# AuxPDU.net
KiCad netlist of a schematic drawn in Altium Designer
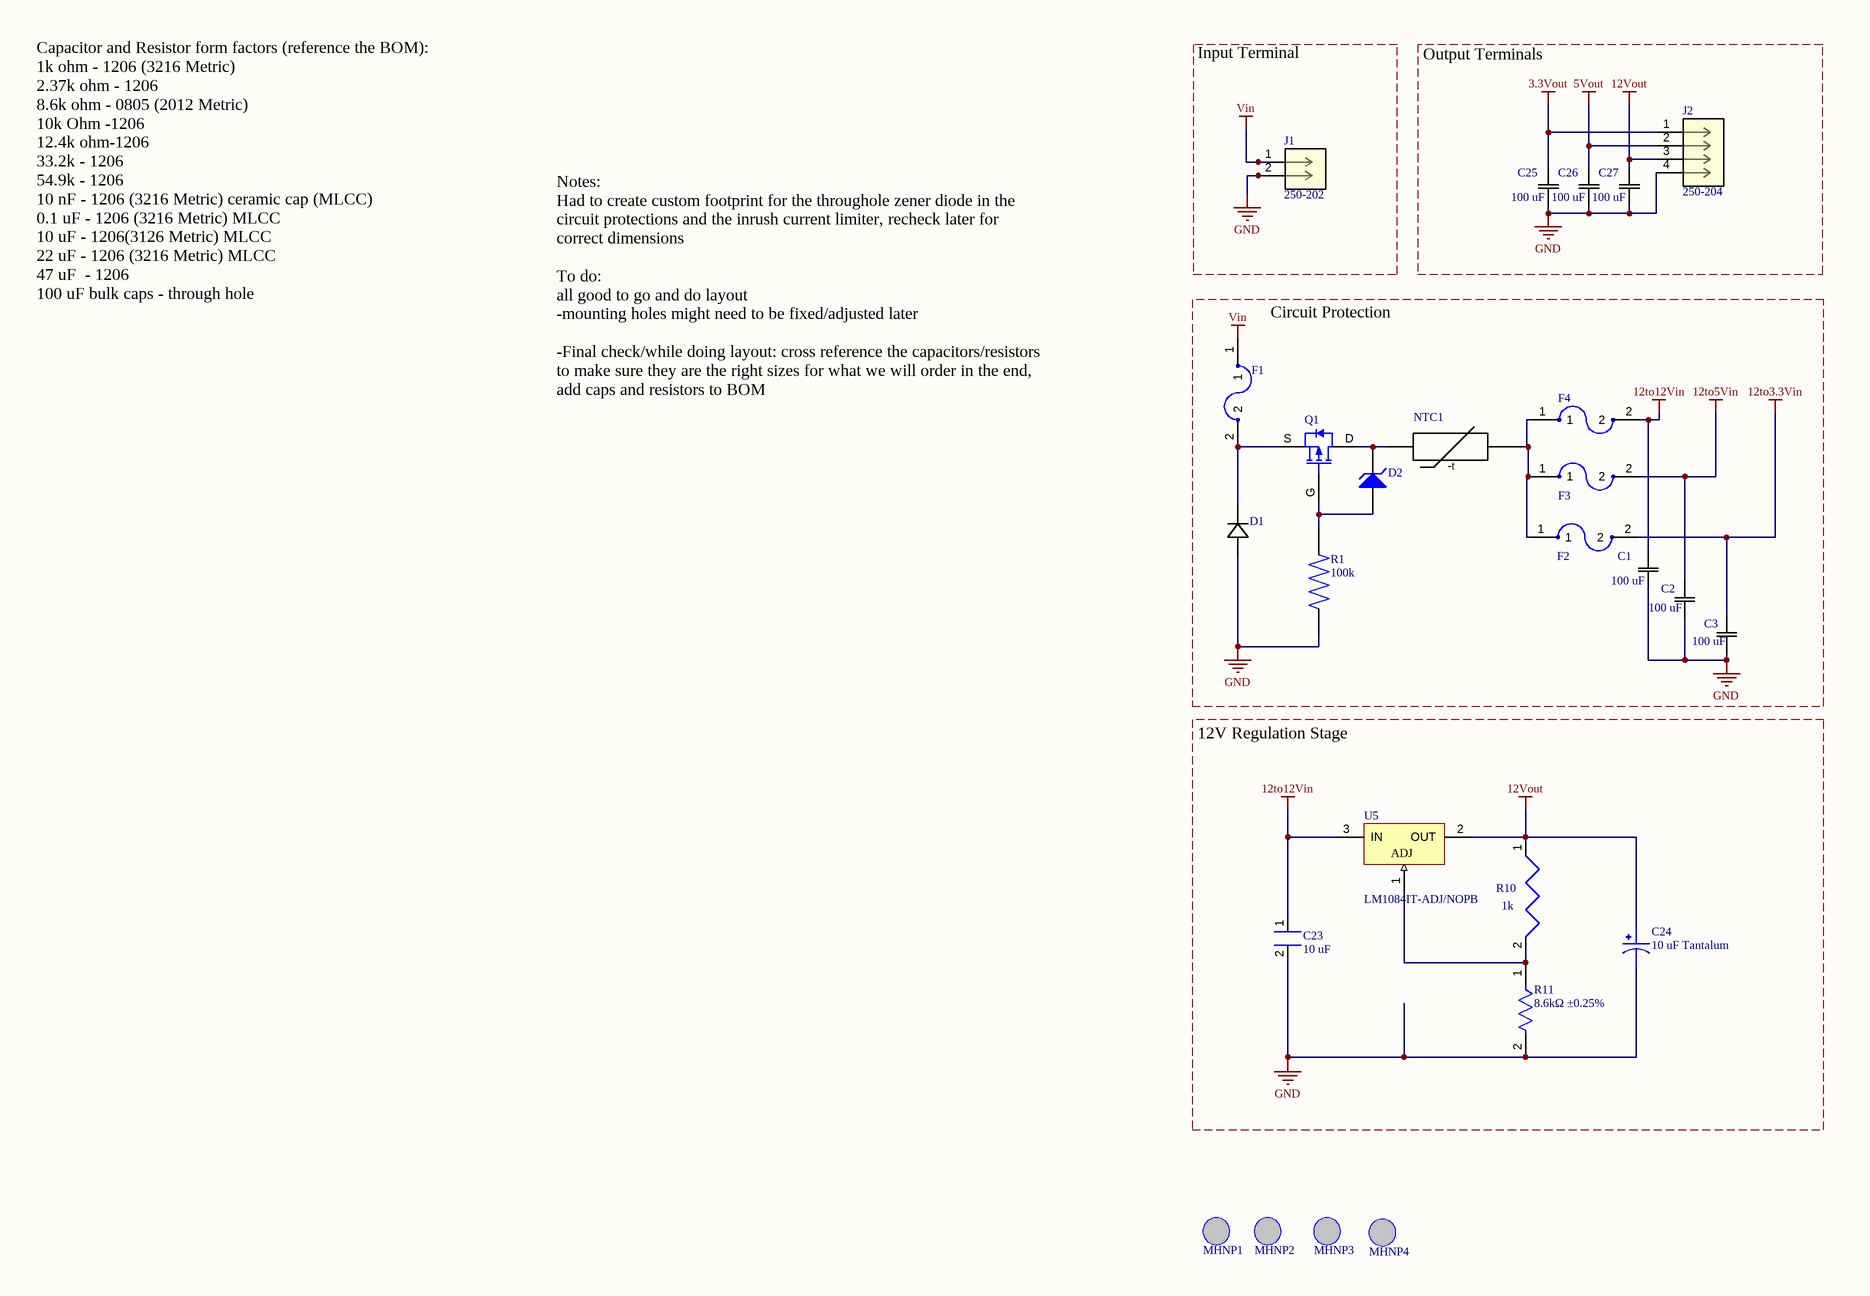
[diagram p0: AuxPDU.SchDoc, left]
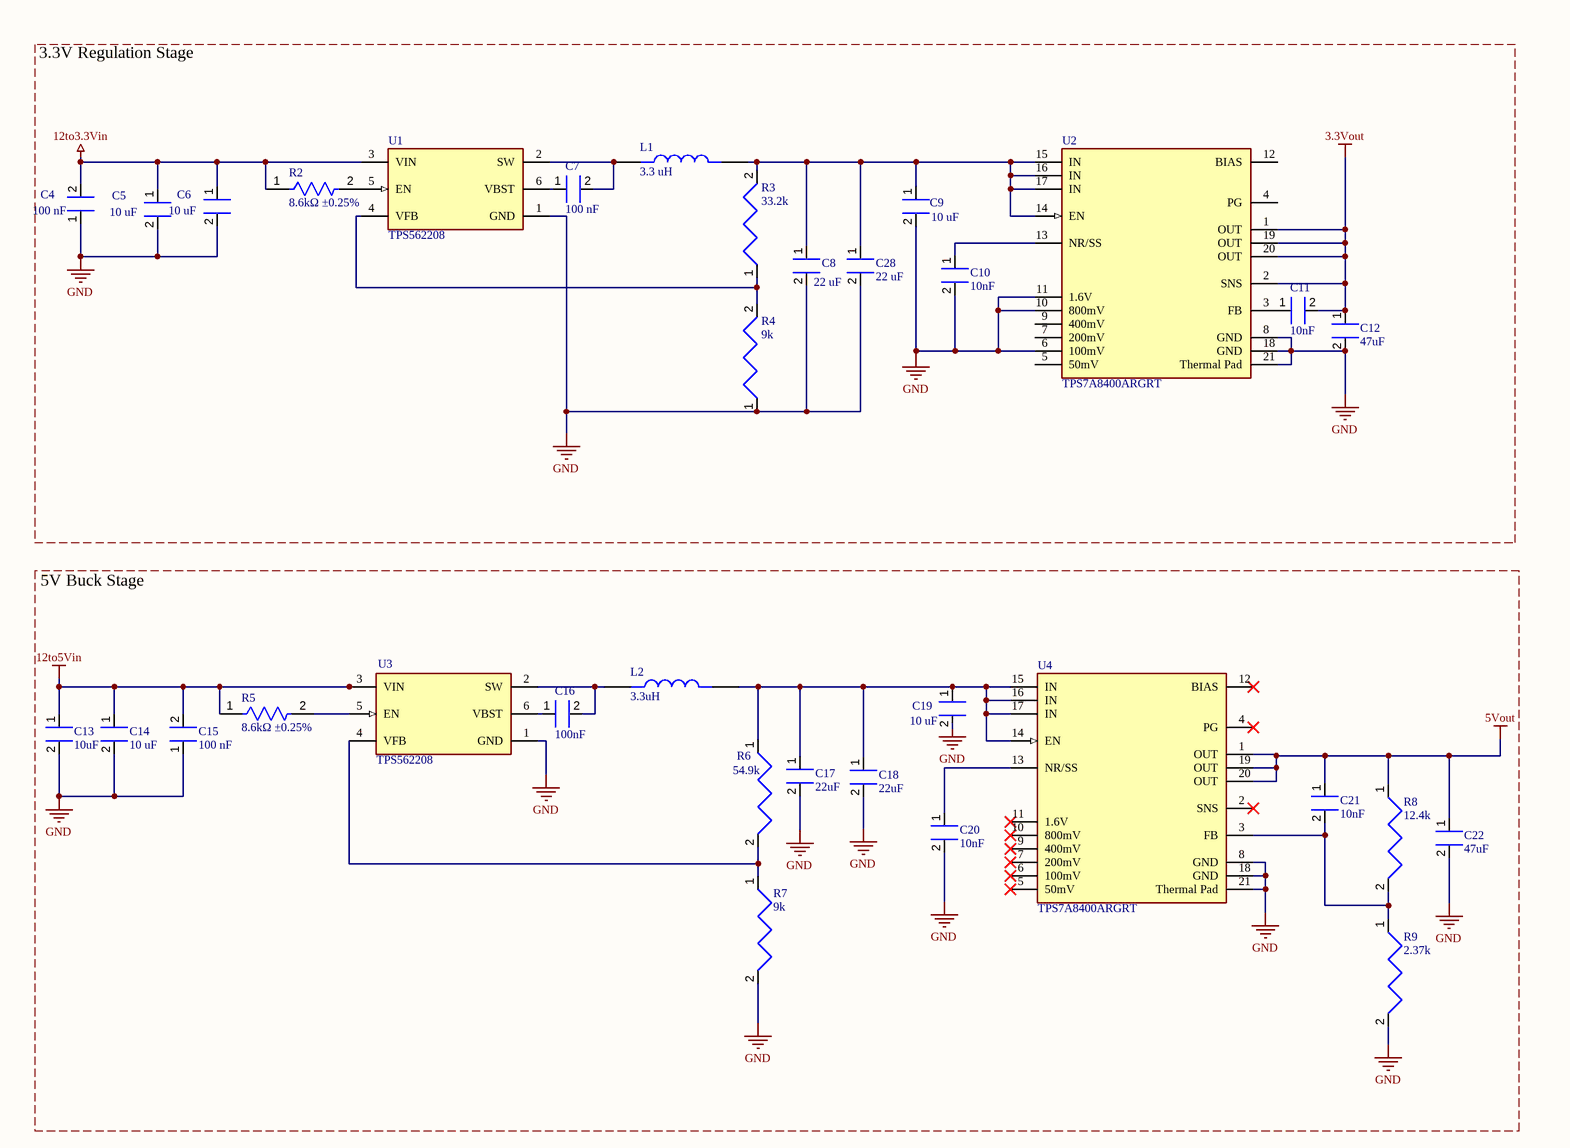
[diagram p1: AuxPDU.SchDoc, right]

(export (version "E")
  (design (tool "Eeschema 10.0.6"))
  (components
    (comp (ref "C1")
      (value "100 uF")
      (footprint "CAP_YX_6P3X11_RUB")
      (description "100 uF electrolytic capacitor")
      (fields
        (field (name "MANUFACTURER_PART_NUMBER") "35ZLH100MEFC6.3X11")
        (field (name "COPYRIGHT") "Copyright (C) 2025 Ultra Librarian. All rights reserved.")
      )
      (libsource (lib "AuxPDU") (part "35ZLH100MEFC6.3X11"))
    )
    (comp (ref "C2")
      (value "100 uF")
      (footprint "CAP_YX_6P3X11_RUB")
      (description "100 uF electrolytic capacitor")
      (fields
        (field (name "MANUFACTURER_PART_NUMBER") "35ZLH100MEFC6.3X11")
        (field (name "COPYRIGHT") "Copyright (C) 2025 Ultra Librarian. All rights reserved.")
      )
      (libsource (lib "AuxPDU") (part "35ZLH100MEFC6.3X11"))
    )
    (comp (ref "C3")
      (value "100 uF")
      (footprint "CAP_YX_6P3X11_RUB")
      (description "100 uF electrolytic capacitor")
      (fields
        (field (name "MANUFACTURER_PART_NUMBER") "35ZLH100MEFC6.3X11")
        (field (name "COPYRIGHT") "Copyright (C) 2025 Ultra Librarian. All rights reserved.")
      )
      (libsource (lib "AuxPDU") (part "35ZLH100MEFC6.3X11"))
    )
    (comp (ref "C4")
      (value "100 nF")
      (footprint "Cap 1206")
      (description "Generic SMD capacitor with 1206 package (3216 metric)")
      (libsource (lib "AuxPDU") (part "Cap 1206"))
    )
    (comp (ref "C5")
      (value "10 uF")
      (footprint "Cap 1206")
      (description "Generic SMD capacitor with 1206 package (3216 metric)")
      (libsource (lib "AuxPDU") (part "Cap 1206"))
    )
    (comp (ref "C6")
      (value "10 uF")
      (footprint "Cap 1206")
      (description "Generic SMD capacitor with 1206 package (3216 metric)")
      (libsource (lib "AuxPDU") (part "Cap 1206"))
    )
    (comp (ref "C7")
      (value "100 nF")
      (footprint "Cap 1206")
      (description "Generic SMD capacitor with 1206 package (3216 metric)")
      (libsource (lib "AuxPDU") (part "Cap 1206"))
    )
    (comp (ref "C8")
      (value "22 uF")
      (footprint "Cap 1206")
      (description "Generic SMD capacitor with 1206 package (3216 metric)")
      (libsource (lib "AuxPDU") (part "Cap 1206"))
    )
    (comp (ref "C9")
      (value "10 uF")
      (footprint "Cap 1206")
      (description "Generic SMD capacitor with 1206 package (3216 metric)")
      (libsource (lib "AuxPDU") (part "Cap 1206"))
    )
    (comp (ref "C10")
      (value "10nF")
      (footprint "Cap 1206")
      (description "Generic SMD capacitor with 1206 package (3216 metric)")
      (libsource (lib "AuxPDU") (part "Cap 1206"))
    )
    (comp (ref "C11")
      (value "10nF")
      (footprint "Cap 1206")
      (description "Generic SMD capacitor with 1206 package (3216 metric)")
      (libsource (lib "AuxPDU") (part "Cap 1206"))
    )
    (comp (ref "C12")
      (value "47uF")
      (footprint "Cap 1206")
      (description "Generic SMD capacitor with 1206 package (3216 metric)")
      (libsource (lib "AuxPDU") (part "Cap 1206"))
    )
    (comp (ref "C13")
      (value "10uF")
      (footprint "Cap 1206")
      (description "Generic SMD capacitor with 1206 package (3216 metric)")
      (libsource (lib "AuxPDU") (part "Cap 1206"))
    )
    (comp (ref "C14")
      (value "10 uF")
      (footprint "Cap 1206")
      (description "Generic SMD capacitor with 1206 package (3216 metric)")
      (libsource (lib "AuxPDU") (part "Cap 1206"))
    )
    (comp (ref "C15")
      (value "100 nF")
      (footprint "Cap 1206")
      (description "Generic SMD capacitor with 1206 package (3216 metric)")
      (libsource (lib "AuxPDU") (part "Cap 1206"))
    )
    (comp (ref "C16")
      (value "100nF")
      (footprint "Cap 1206")
      (description "Generic SMD capacitor with 1206 package (3216 metric)")
      (libsource (lib "AuxPDU") (part "Cap 1206"))
    )
    (comp (ref "C17")
      (value "22uF")
      (footprint "Cap 1206")
      (description "Generic SMD capacitor with 1206 package (3216 metric)")
      (libsource (lib "AuxPDU") (part "Cap 1206"))
    )
    (comp (ref "C18")
      (value "22uF")
      (footprint "Cap 1206")
      (description "Generic SMD capacitor with 1206 package (3216 metric)")
      (libsource (lib "AuxPDU") (part "Cap 1206"))
    )
    (comp (ref "C19")
      (value "10 uF")
      (footprint "Cap 1206")
      (description "Generic SMD capacitor with 1206 package (3216 metric)")
      (libsource (lib "AuxPDU") (part "Cap 1206"))
    )
    (comp (ref "C20")
      (value "10nF")
      (footprint "Cap 1206")
      (description "Generic SMD capacitor with 1206 package (3216 metric)")
      (libsource (lib "AuxPDU") (part "Cap 1206"))
    )
    (comp (ref "C21")
      (value "10nF")
      (footprint "Cap 1206")
      (description "Generic SMD capacitor with 1206 package (3216 metric)")
      (libsource (lib "AuxPDU") (part "Cap 1206"))
    )
    (comp (ref "C22")
      (value "47uF")
      (footprint "Cap 1206")
      (description "Generic SMD capacitor with 1206 package (3216 metric)")
      (libsource (lib "AuxPDU") (part "Cap 1206"))
    )
    (comp (ref "C23")
      (value "10 uF")
      (footprint "Cap 1206")
      (description "Generic SMD capacitor with 1206 package (3216 metric)")
      (libsource (lib "AuxPDU") (part "Cap 1206"))
    )
    (comp (ref "C24")
      (value "10 uF Tantalum")
      (footprint "CAPMP3216X180N")
      (description "10 ÂµF Molded Tantalum Capacitors 16 V 1206 (3216 Metric) 3Ohm")
      (fields (field (name "MF") "KYOCERA AVX") (field (name "MP") "TAJA106K016RNJ"))
      (libsource (lib "AuxPDU") (part "TAJA106K016RNJ"))
    )
    (comp (ref "C25")
      (value "100 uF")
      (footprint "CAP_YX_6P3X11_RUB")
      (description "100 uF electrolytic capacitor")
      (fields
        (field (name "MANUFACTURER_PART_NUMBER") "35ZLH100MEFC6.3X11")
        (field (name "COPYRIGHT") "Copyright (C) 2025 Ultra Librarian. All rights reserved.")
      )
      (libsource (lib "AuxPDU") (part "35ZLH100MEFC6.3X11"))
    )
    (comp (ref "C26")
      (value "100 uF")
      (footprint "CAP_YX_6P3X11_RUB")
      (description "100 uF electrolytic capacitor")
      (fields
        (field (name "MANUFACTURER_PART_NUMBER") "35ZLH100MEFC6.3X11")
        (field (name "COPYRIGHT") "Copyright (C) 2025 Ultra Librarian. All rights reserved.")
      )
      (libsource (lib "AuxPDU") (part "35ZLH100MEFC6.3X11"))
    )
    (comp (ref "C27")
      (value "100 uF")
      (footprint "CAP_YX_6P3X11_RUB")
      (description "100 uF electrolytic capacitor")
      (fields
        (field (name "MANUFACTURER_PART_NUMBER") "35ZLH100MEFC6.3X11")
        (field (name "COPYRIGHT") "Copyright (C) 2025 Ultra Librarian. All rights reserved.")
      )
      (libsource (lib "AuxPDU") (part "35ZLH100MEFC6.3X11"))
    )
    (comp (ref "C28")
      (value "22 uF")
      (footprint "Cap 1206")
      (description "Generic SMD capacitor with 1206 package (3216 metric)")
      (libsource (lib "AuxPDU") (part "Cap 1206"))
    )
    (comp (ref "D1")
      (value "TVS DIODE 14VWM 23.2VC DO214AB")
      (footprint "SMCJSeries_LTF-M")
      (description "Unidirectional")
      (libsource (lib "AuxPDU") (part "SMCJ14A"))
    )
    (comp (ref "D2")
      (value "DIODE ZENER 10V 500MW DO35")
      (footprint "BZX79C10")
      (libsource (lib "AuxPDU") (part "BZX79C10"))
    )
    (comp (ref "F1")
      (value "~")
      (footprint "CHIP_2920L_7P98X5P44_LTF-M")
      (description "Description")
      (fields
        (field (name "MANUFACTURER_PART_NUMBER") "2920L150DR")
        (field (name "COPYRIGHT") "Copyright (C) 2025 Ultra Librarian. All rights reserved.")
      )
      (libsource (lib "AuxPDU") (part "2920L150DR"))
    )
    (comp (ref "F2")
      (value "1812L110/33MR")
      (footprint "1812L110_33MR")
      (fields (field (name "MF") "{'manufacturer': u'Littelfuse Inc.'}"))
      (libsource (lib "AuxPDU") (part "1812L110/33MR"))
    )
    (comp (ref "F3")
      (value "1812L110/33MR")
      (footprint "1812L110_33MR")
      (fields (field (name "MF") "{'manufacturer': u'Littelfuse Inc.'}"))
      (libsource (lib "AuxPDU") (part "1812L110/33MR"))
    )
    (comp (ref "F4")
      (value "~")
      (footprint "CHIP_2920L_7P98X5P44_LTF-M")
      (description "Description")
      (fields
        (field (name "MANUFACTURER_PART_NUMBER") "2920L150DR")
        (field (name "COPYRIGHT") "Copyright (C) 2025 Ultra Librarian. All rights reserved.")
      )
      (libsource (lib "AuxPDU") (part "2920L150DR"))
    )
    (comp (ref "J1")
      (value "250-202")
      (footprint "CONN2_250-202_WAG")
      (description "Description")
      (fields (field (name "COPYRIGHT") "Copyright (C) 2025 Ultra Librarian. All rights reserved."))
      (libsource (lib "AuxPDU") (part "250-202"))
    )
    (comp (ref "J2")
      (value "250-204")
      (footprint "CONN4_250-204_WAG")
      (description "Description")
      (fields (field (name "COPYRIGHT") "Copyright (C) 2025 Ultra Librarian. All rights reserved."))
      (libsource (lib "AuxPDU") (part "250-204"))
    )
    (comp (ref "L1")
      (value "3.3 uH")
      (footprint "IND_MSS7341-332NLD")
      (description "3.3 ÂµH Shielded Drum Core Inductor 3.95 A 18mOhm Max Nonstandard")
      (fields (field (name "MF") "Coilcraft") (field (name "MP") "MSS7341-332NLD"))
      (libsource (lib "AuxPDU") (part "MSS7341-332NLD"))
    )
    (comp (ref "L2")
      (value "3.3uH")
      (footprint "IND_MSS7341-332NLD")
      (description "3.3 ÂµH Shielded Drum Core Inductor 3.95 A 18mOhm Max Nonstandard")
      (fields (field (name "MF") "Coilcraft") (field (name "MP") "MSS7341-332NLD"))
      (libsource (lib "AuxPDU") (part "MSS7341-332NLD"))
    )
    (comp (ref "MHNP1")
      (value "Mounting Hole Non-Plated 3.2 mm")
      (footprint "MTHNP3P2MM")
      (libsource (lib "AuxPDU") (part "MTHNP3P2MM"))
    )
    (comp (ref "MHNP2")
      (value "Mounting Hole Non-Plated 3.2 mm")
      (footprint "MTHNP3P2MM")
      (libsource (lib "AuxPDU") (part "MTHNP3P2MM"))
    )
    (comp (ref "MHNP3")
      (value "Mounting Hole Non-Plated 3.2 mm")
      (footprint "MTHNP3P2MM")
      (libsource (lib "AuxPDU") (part "MTHNP3P2MM"))
    )
    (comp (ref "MHNP4")
      (value "Mounting Hole Non-Plated 3.2 mm")
      (footprint "MTHNP3P2MM")
      (libsource (lib "AuxPDU") (part "MTHNP3P2MM"))
    )
    (comp (ref "NTC1")
      (value "ICL 20 OHM 25% 10A 29MM")
      (footprint "AS3220010")
      (libsource (lib "AuxPDU") (part "AS3220010"))
    )
    (comp (ref "Q1")
      (value "MOSFET P-CH 50V 9.7A TO220AB")
      (footprint "IRF9Z20PBF")
      (libsource (lib "AuxPDU") (part "IRF9Z20PBF"))
    )
    (comp (ref "R1")
      (value "100k")
      (footprint "RESC3116X65N")
      (fields (field (name "MF") "{'manufacturer': u'YAGEO'}") (field (name "MP") "RC1206FR-10100KL"))
      (libsource (lib "AuxPDU") (part "RC1206FR-10100KL"))
    )
    (comp (ref "R2")
      (value "8.6kΩ ±0.25%")
      (footprint "FP-RK73G2A-MFG")
      (description "8.06kΩ ±0.25% 0.125W Chip Resistor 0805 Thick Film AEC-Q200 Qualified")
      (libsource (lib "Altium Content Vault") (part "1029c3af85768c4190bb7ad29bc67b5"))
    )
    (comp (ref "R3")
      (value "33.2k")
      (footprint "Cap 1206")
      (description "Generic SMD resistor with 1206 package (3216 metric)")
      (libsource (lib "AuxPDU") (part "Res 1206"))
    )
    (comp (ref "R4")
      (value "9k")
      (footprint "Cap 1206")
      (description "Generic SMD resistor with 1206 package (3216 metric)")
      (libsource (lib "AuxPDU") (part "Res 1206"))
    )
    (comp (ref "R5")
      (value "8.6kΩ ±0.25%")
      (footprint "FP-RK73G2A-MFG")
      (description "8.06kΩ ±0.25% 0.125W Chip Resistor 0805 Thick Film AEC-Q200 Qualified")
      (libsource (lib "Altium Content Vault") (part "1029c3af85768c4190bb7ad29bc67b5"))
    )
    (comp (ref "R6")
      (value "54.9k")
      (footprint "Cap 1206")
      (description "Generic SMD resistor with 1206 package (3216 metric)")
      (libsource (lib "AuxPDU") (part "Res 1206"))
    )
    (comp (ref "R7")
      (value "9k")
      (footprint "Cap 1206")
      (description "Generic SMD resistor with 1206 package (3216 metric)")
      (libsource (lib "AuxPDU") (part "Res 1206"))
    )
    (comp (ref "R8")
      (value "12.4k")
      (footprint "Cap 1206")
      (description "Generic SMD resistor with 1206 package (3216 metric)")
      (libsource (lib "AuxPDU") (part "Res 1206"))
    )
    (comp (ref "R9")
      (value "2.37k")
      (footprint "Cap 1206")
      (description "Generic SMD resistor with 1206 package (3216 metric)")
      (libsource (lib "AuxPDU") (part "Res 1206"))
    )
    (comp (ref "R10")
      (value "1k")
      (footprint "Cap 1206")
      (description "Generic SMD resistor with 1206 package (3216 metric)")
      (libsource (lib "AuxPDU") (part "Res 1206"))
    )
    (comp (ref "R11")
      (value "8.6kΩ ±0.25%")
      (footprint "FP-RK73G2A-MFG")
      (description "8.06kΩ ±0.25% 0.125W Chip Resistor 0805 Thick Film AEC-Q200 Qualified")
      (libsource (lib "Altium Content Vault") (part "1029c3af85768c4190bb7ad29bc67b5"))
    )
    (comp (ref "U1")
      (value "TPS562208")
      (footprint "TPS562208")
      (description "Buck Switching Regulator IC Positive Adjustable 0.768V 1 Output 2A SOT-23-6 Thin, TSOT-23-6")
      (libsource (lib "AuxPDU") (part "TPS562208"))
    )
    (comp (ref "U2")
      (value "TPS7A8400ARGRT")
      (footprint "TPS7A8400ARGRT")
      (description "Linear Voltage Regulator IC Positive Adjustable/Programmable 1 Output 3A")
      (libsource (lib "AuxPDU") (part "TPS7A8400ARGRT"))
    )
    (comp (ref "U3")
      (value "TPS562208")
      (footprint "TPS562208")
      (description "Buck Switching Regulator IC Positive Adjustable 0.768V 1 Output 2A SOT-23-6 Thin, TSOT-23-6")
      (libsource (lib "AuxPDU") (part "TPS562208"))
    )
    (comp (ref "U4")
      (value "TPS7A8400ARGRT")
      (footprint "TPS7A8400ARGRT")
      (description "Linear Voltage Regulator IC Positive Adjustable/Programmable 1 Output 3A")
      (libsource (lib "AuxPDU") (part "TPS7A8400ARGRT"))
    )
    (comp (ref "U5")
      (value "LM1084IT-ADJ/NOPB")
      (footprint "NDE0003A")
      (description "5A Low Dropout Positive Regulators, 3-pin TO-220, Pb-Free")
      (fields (field (name "MANUFACTURER") "Texas Instruments"))
      (libsource (lib "Altium Content Vault") (part "PM-REG-LM1086ADJ-SIL3"))
    )
  )
  (nets
    (net (code "1") (name "3.3Vout") (class "Default")
      (node (ref "C11") (pin "2") (pinfunction "2_2") (pintype "passive"))
      (node (ref "C12") (pin "1") (pinfunction "1_1") (pintype "passive"))
      (node (ref "C25") (pin "2") (pinfunction "2_2") (pintype "passive"))
      (node (ref "J2") (pin "1") (pinfunction "1_1") (pintype "passive"))
      (node (ref "U2") (pin "1") (pinfunction "OUT_1") (pintype "passive"))
      (node (ref "U2") (pin "19") (pinfunction "OUT_19") (pintype "passive"))
      (node (ref "U2") (pin "2") (pinfunction "SNS_2") (pintype "passive"))
      (node (ref "U2") (pin "20") (pinfunction "OUT_20") (pintype "passive"))
    )
    (net (code "2") (name "5Vout") (class "Default")
      (node (ref "C21") (pin "1") (pinfunction "1_1") (pintype "passive"))
      (node (ref "C22") (pin "1") (pinfunction "1_1") (pintype "passive"))
      (node (ref "C26") (pin "2") (pinfunction "2_2") (pintype "passive"))
      (node (ref "J2") (pin "2") (pinfunction "2_2") (pintype "passive"))
      (node (ref "R8") (pin "1") (pinfunction "1_1") (pintype "passive"))
      (node (ref "U4") (pin "1") (pinfunction "OUT_1") (pintype "passive"))
      (node (ref "U4") (pin "19") (pinfunction "OUT_19") (pintype "passive"))
      (node (ref "U4") (pin "20") (pinfunction "OUT_20") (pintype "passive"))
    )
    (net (code "3") (name "12Vout") (class "Default")
      (node (ref "C24") (pin "1") (pinfunction "1_1") (pintype "passive"))
      (node (ref "C27") (pin "2") (pinfunction "2_2") (pintype "passive"))
      (node (ref "J2") (pin "3") (pinfunction "3_3") (pintype "passive"))
      (node (ref "R10") (pin "1") (pinfunction "1_1") (pintype "passive"))
      (node (ref "U5") (pin "2") (pinfunction "OUT_2") (pintype "power_in"))
    )
    (net (code "4") (name "12to3.3Vin") (class "Default")
      (node (ref "C3") (pin "2") (pinfunction "2_2") (pintype "passive"))
      (node (ref "C4") (pin "2") (pinfunction "2_2") (pintype "passive"))
      (node (ref "C5") (pin "1") (pinfunction "1_1") (pintype "passive"))
      (node (ref "C6") (pin "1") (pinfunction "1_1") (pintype "passive"))
      (node (ref "F2") (pin "2") (pinfunction "2_2") (pintype "passive"))
      (node (ref "R2") (pin "1") (pinfunction "1_1") (pintype "passive"))
      (node (ref "U1") (pin "3") (pinfunction "VIN_3") (pintype "power_in"))
    )
    (net (code "5") (name "12to5Vin") (class "Default")
      (node (ref "C13") (pin "1") (pinfunction "1_1") (pintype "passive"))
      (node (ref "C14") (pin "1") (pinfunction "1_1") (pintype "passive"))
      (node (ref "C15") (pin "2") (pinfunction "2_2") (pintype "passive"))
      (node (ref "C2") (pin "2") (pinfunction "2_2") (pintype "passive"))
      (node (ref "F3") (pin "2") (pinfunction "2_2") (pintype "passive"))
      (node (ref "R5") (pin "1") (pinfunction "1_1") (pintype "passive"))
      (node (ref "U3") (pin "3") (pinfunction "VIN_3") (pintype "power_in"))
    )
    (net (code "6") (name "12to12Vin") (class "Default")
      (node (ref "C1") (pin "2") (pinfunction "2_2") (pintype "passive"))
      (node (ref "C23") (pin "1") (pinfunction "1_1") (pintype "passive"))
      (node (ref "F4") (pin "2") (pinfunction "2_2") (pintype "passive"))
      (node (ref "U5") (pin "3") (pinfunction "IN_3") (pintype "power_in"))
    )
    (net (code "7") (name "GND") (class "Default")
      (node (ref "C1") (pin "1") (pinfunction "1_1") (pintype "passive"))
      (node (ref "C10") (pin "2") (pinfunction "2_2") (pintype "passive"))
      (node (ref "C12") (pin "2") (pinfunction "2_2") (pintype "passive"))
      (node (ref "C13") (pin "2") (pinfunction "2_2") (pintype "passive"))
      (node (ref "C14") (pin "2") (pinfunction "2_2") (pintype "passive"))
      (node (ref "C15") (pin "1") (pinfunction "1_1") (pintype "passive"))
      (node (ref "C17") (pin "2") (pinfunction "2_2") (pintype "passive"))
      (node (ref "C18") (pin "2") (pinfunction "2_2") (pintype "passive"))
      (node (ref "C19") (pin "2") (pinfunction "2_2") (pintype "passive"))
      (node (ref "C2") (pin "1") (pinfunction "1_1") (pintype "passive"))
      (node (ref "C20") (pin "2") (pinfunction "2_2") (pintype "passive"))
      (node (ref "C22") (pin "2") (pinfunction "2_2") (pintype "passive"))
      (node (ref "C23") (pin "2") (pinfunction "2_2") (pintype "passive"))
      (node (ref "C24") (pin "2") (pinfunction "2_2") (pintype "passive"))
      (node (ref "C25") (pin "1") (pinfunction "1_1") (pintype "passive"))
      (node (ref "C26") (pin "1") (pinfunction "1_1") (pintype "passive"))
      (node (ref "C27") (pin "1") (pinfunction "1_1") (pintype "passive"))
      (node (ref "C28") (pin "2") (pinfunction "2_2") (pintype "passive"))
      (node (ref "C3") (pin "1") (pinfunction "1_1") (pintype "passive"))
      (node (ref "C4") (pin "1") (pinfunction "1_1") (pintype "passive"))
      (node (ref "C5") (pin "2") (pinfunction "2_2") (pintype "passive"))
      (node (ref "C6") (pin "2") (pinfunction "2_2") (pintype "passive"))
      (node (ref "C8") (pin "2") (pinfunction "2_2") (pintype "passive"))
      (node (ref "C9") (pin "2") (pinfunction "2_2") (pintype "passive"))
      (node (ref "D1") (pin "2") (pinfunction "2_2") (pintype "passive"))
      (node (ref "J1") (pin "2") (pinfunction "2_2") (pintype "passive"))
      (node (ref "J2") (pin "4") (pinfunction "4_4") (pintype "passive"))
      (node (ref "R1") (pin "1") (pinfunction "1_1") (pintype "passive"))
      (node (ref "R11") (pin "2") (pinfunction "2_2") (pintype "passive"))
      (node (ref "R4") (pin "1") (pinfunction "1_1") (pintype "passive"))
      (node (ref "R7") (pin "2") (pinfunction "2_2") (pintype "passive"))
      (node (ref "R9") (pin "2") (pinfunction "2_2") (pintype "passive"))
      (node (ref "U1") (pin "1") (pinfunction "GND_1") (pintype "power_in"))
      (node (ref "U2") (pin "10") (pinfunction "800mV_10") (pintype "passive"))
      (node (ref "U2") (pin "11") (pinfunction "1.6V_11") (pintype "passive"))
      (node (ref "U2") (pin "18") (pinfunction "GND_18") (pintype "power_in"))
      (node (ref "U2") (pin "21") (pinfunction "Thermal_Pad_21") (pintype "power_in"))
      (node (ref "U2") (pin "6") (pinfunction "100mV_6") (pintype "passive"))
      (node (ref "U2") (pin "8") (pinfunction "GND_8") (pintype "power_in"))
      (node (ref "U3") (pin "1") (pinfunction "GND_1") (pintype "power_in"))
      (node (ref "U4") (pin "18") (pinfunction "GND_18") (pintype "power_in"))
      (node (ref "U4") (pin "21") (pinfunction "Thermal_Pad_21") (pintype "power_in"))
      (node (ref "U4") (pin "8") (pinfunction "GND_8") (pintype "power_in"))
    )
    (net (code "8") (name "Net-(D2-A)") (class "Default")
      (node (ref "D2") (pin "1") (pinfunction "A_1") (pintype "passive"))
      (node (ref "Q1") (pin "G") (pinfunction "GATE_G") (pintype "passive"))
      (node (ref "R1") (pin "2") (pinfunction "2_2") (pintype "passive"))
    )
    (net (code "9") (name "Net-(D2-K)") (class "Default")
      (node (ref "D2") (pin "2") (pinfunction "K_2") (pintype "passive"))
      (node (ref "NTC1") (pin "1") (pinfunction "2_1") (pintype "passive"))
      (node (ref "Q1") (pin "D") (pinfunction "DRAIN_D") (pintype "passive"))
    )
    (net (code "10") (name "Net-(F2-Pad1)") (class "Default")
      (node (ref "F2") (pin "1") (pinfunction "1_1") (pintype "passive"))
      (node (ref "F3") (pin "1") (pinfunction "1_1") (pintype "passive"))
      (node (ref "F4") (pin "1") (pinfunction "1_1") (pintype "passive"))
      (node (ref "NTC1") (pin "2") (pinfunction "2_2") (pintype "passive"))
    )
    (net (code "11") (name "Net-(Q1-SOURCE)") (class "Default")
      (node (ref "D1") (pin "1") (pinfunction "1_1") (pintype "passive"))
      (node (ref "F1") (pin "2") (pinfunction "2_2") (pintype "passive"))
      (node (ref "Q1") (pin "S") (pinfunction "SOURCE_S") (pintype "passive"))
    )
    (net (code "12") (name "Net-(U1-EN)") (class "Default")
      (node (ref "R2") (pin "2") (pinfunction "2_2") (pintype "passive"))
      (node (ref "U1") (pin "5") (pinfunction "EN_5") (pintype "input"))
    )
    (net (code "13") (name "Net-(U1-SW)") (class "Default")
      (node (ref "C7") (pin "2") (pinfunction "2_2") (pintype "passive"))
      (node (ref "L1") (pin "1") (pinfunction "1_1") (pintype "passive"))
      (node (ref "U1") (pin "2") (pinfunction "SW_2") (pintype "passive"))
    )
    (net (code "14") (name "Net-(U1-VBST)") (class "Default")
      (node (ref "C7") (pin "1") (pinfunction "1_1") (pintype "passive"))
      (node (ref "U1") (pin "6") (pinfunction "VBST_6") (pintype "passive"))
    )
    (net (code "15") (name "Net-(U1-VFB)") (class "Default")
      (node (ref "R3") (pin "1") (pinfunction "1_1") (pintype "passive"))
      (node (ref "R4") (pin "2") (pinfunction "2_2") (pintype "passive"))
      (node (ref "U1") (pin "4") (pinfunction "VFB_4") (pintype "passive"))
    )
    (net (code "16") (name "Net-(U2-EN)") (class "Default")
      (node (ref "C28") (pin "1") (pinfunction "1_1") (pintype "passive"))
      (node (ref "C8") (pin "1") (pinfunction "1_1") (pintype "passive"))
      (node (ref "C9") (pin "1") (pinfunction "1_1") (pintype "passive"))
      (node (ref "L1") (pin "2") (pinfunction "2_2") (pintype "passive"))
      (node (ref "R3") (pin "2") (pinfunction "2_2") (pintype "passive"))
      (node (ref "U2") (pin "14") (pinfunction "EN_14") (pintype "input"))
      (node (ref "U2") (pin "15") (pinfunction "IN_15") (pintype "power_in"))
      (node (ref "U2") (pin "16") (pinfunction "IN_16") (pintype "power_in"))
      (node (ref "U2") (pin "17") (pinfunction "IN_17") (pintype "power_in"))
    )
    (net (code "17") (name "Net-(U2-FB)") (class "Default")
      (node (ref "C11") (pin "1") (pinfunction "1_1") (pintype "passive"))
      (node (ref "U2") (pin "3") (pinfunction "FB_3") (pintype "passive"))
    )
    (net (code "18") (name "Net-(U2-NR{slash}SS)") (class "Default")
      (node (ref "C10") (pin "1") (pinfunction "1_1") (pintype "passive"))
      (node (ref "U2") (pin "13") (pinfunction "NR/SS_13") (pintype "passive"))
    )
    (net (code "19") (name "Net-(U3-EN)") (class "Default")
      (node (ref "R5") (pin "2") (pinfunction "2_2") (pintype "passive"))
      (node (ref "U3") (pin "5") (pinfunction "EN_5") (pintype "input"))
    )
    (net (code "20") (name "Net-(U3-SW)") (class "Default")
      (node (ref "C16") (pin "2") (pinfunction "2_2") (pintype "passive"))
      (node (ref "L2") (pin "1") (pinfunction "1_1") (pintype "passive"))
      (node (ref "U3") (pin "2") (pinfunction "SW_2") (pintype "passive"))
    )
    (net (code "21") (name "Net-(U3-VBST)") (class "Default")
      (node (ref "C16") (pin "1") (pinfunction "1_1") (pintype "passive"))
      (node (ref "U3") (pin "6") (pinfunction "VBST_6") (pintype "passive"))
    )
    (net (code "22") (name "Net-(U3-VFB)") (class "Default")
      (node (ref "R6") (pin "2") (pinfunction "2_2") (pintype "passive"))
      (node (ref "R7") (pin "1") (pinfunction "1_1") (pintype "passive"))
      (node (ref "U3") (pin "4") (pinfunction "VFB_4") (pintype "passive"))
    )
    (net (code "23") (name "Net-(U4-EN)") (class "Default")
      (node (ref "C17") (pin "1") (pinfunction "1_1") (pintype "passive"))
      (node (ref "C18") (pin "1") (pinfunction "1_1") (pintype "passive"))
      (node (ref "C19") (pin "1") (pinfunction "1_1") (pintype "passive"))
      (node (ref "L2") (pin "2") (pinfunction "2_2") (pintype "passive"))
      (node (ref "R6") (pin "1") (pinfunction "1_1") (pintype "passive"))
      (node (ref "U4") (pin "14") (pinfunction "EN_14") (pintype "input"))
      (node (ref "U4") (pin "15") (pinfunction "IN_15") (pintype "power_in"))
      (node (ref "U4") (pin "16") (pinfunction "IN_16") (pintype "power_in"))
      (node (ref "U4") (pin "17") (pinfunction "IN_17") (pintype "power_in"))
    )
    (net (code "24") (name "Net-(U4-FB)") (class "Default")
      (node (ref "C21") (pin "2") (pinfunction "2_2") (pintype "passive"))
      (node (ref "R8") (pin "2") (pinfunction "2_2") (pintype "passive"))
      (node (ref "R9") (pin "1") (pinfunction "1_1") (pintype "passive"))
      (node (ref "U4") (pin "3") (pinfunction "FB_3") (pintype "passive"))
    )
    (net (code "25") (name "Net-(U4-NR{slash}SS)") (class "Default")
      (node (ref "C20") (pin "1") (pinfunction "1_1") (pintype "passive"))
      (node (ref "U4") (pin "13") (pinfunction "NR/SS_13") (pintype "passive"))
    )
    (net (code "26") (name "Net-(U5-ADJ)") (class "Default")
      (node (ref "R10") (pin "2") (pinfunction "2_2") (pintype "passive"))
      (node (ref "R11") (pin "1") (pinfunction "1_1") (pintype "passive"))
      (node (ref "U5") (pin "1") (pinfunction "ADJ_1") (pintype "input"))
    )
    (net (code "27") (name "Vin") (class "Default")
      (node (ref "F1") (pin "1") (pinfunction "1_1") (pintype "passive"))
      (node (ref "J1") (pin "1") (pinfunction "1_1") (pintype "passive"))
    )
    (net (code "28") (name "unconnected-(U2-50mV-Pad5)") (class "Default")
      (node (ref "U2") (pin "5") (pinfunction "50mV_5") (pintype "passive"))
    )
    (net (code "29") (name "unconnected-(U2-200mV-Pad7)") (class "Default")
      (node (ref "U2") (pin "7") (pinfunction "200mV_7") (pintype "passive"))
    )
    (net (code "30") (name "unconnected-(U2-400mV-Pad9)") (class "Default")
      (node (ref "U2") (pin "9") (pinfunction "400mV_9") (pintype "passive"))
    )
    (net (code "31") (name "unconnected-(U2-BIAS-Pad12)") (class "Default")
      (node (ref "U2") (pin "12") (pinfunction "BIAS_12") (pintype "passive"))
    )
    (net (code "32") (name "unconnected-(U2-PG-Pad4)") (class "Default")
      (node (ref "U2") (pin "4") (pinfunction "PG_4") (pintype "open_collector"))
    )
    (net (code "33") (name "unconnected-(U4-1.6V-Pad11)") (class "Default")
      (node (ref "U4") (pin "11") (pinfunction "1.6V_11") (pintype "passive+no_connect"))
    )
    (net (code "34") (name "unconnected-(U4-50mV-Pad5)") (class "Default")
      (node (ref "U4") (pin "5") (pinfunction "50mV_5") (pintype "passive+no_connect"))
    )
    (net (code "35") (name "unconnected-(U4-100mV-Pad6)") (class "Default")
      (node (ref "U4") (pin "6") (pinfunction "100mV_6") (pintype "passive+no_connect"))
    )
    (net (code "36") (name "unconnected-(U4-200mV-Pad7)") (class "Default")
      (node (ref "U4") (pin "7") (pinfunction "200mV_7") (pintype "passive+no_connect"))
    )
    (net (code "37") (name "unconnected-(U4-400mV-Pad9)") (class "Default")
      (node (ref "U4") (pin "9") (pinfunction "400mV_9") (pintype "passive+no_connect"))
    )
    (net (code "38") (name "unconnected-(U4-800mV-Pad10)") (class "Default")
      (node (ref "U4") (pin "10") (pinfunction "800mV_10") (pintype "passive+no_connect"))
    )
    (net (code "39") (name "unconnected-(U4-BIAS-Pad12)") (class "Default")
      (node (ref "U4") (pin "12") (pinfunction "BIAS_12") (pintype "passive+no_connect"))
    )
    (net (code "40") (name "unconnected-(U4-PG-Pad4)") (class "Default")
      (node (ref "U4") (pin "4") (pinfunction "PG_4") (pintype "open_collector+no_connect"))
    )
    (net (code "41") (name "unconnected-(U4-SNS-Pad2)") (class "Default")
      (node (ref "U4") (pin "2") (pinfunction "SNS_2") (pintype "passive+no_connect"))
    )
  )
)
